# USB.net
KiCad netlist of a schematic drawn in Altium Designer
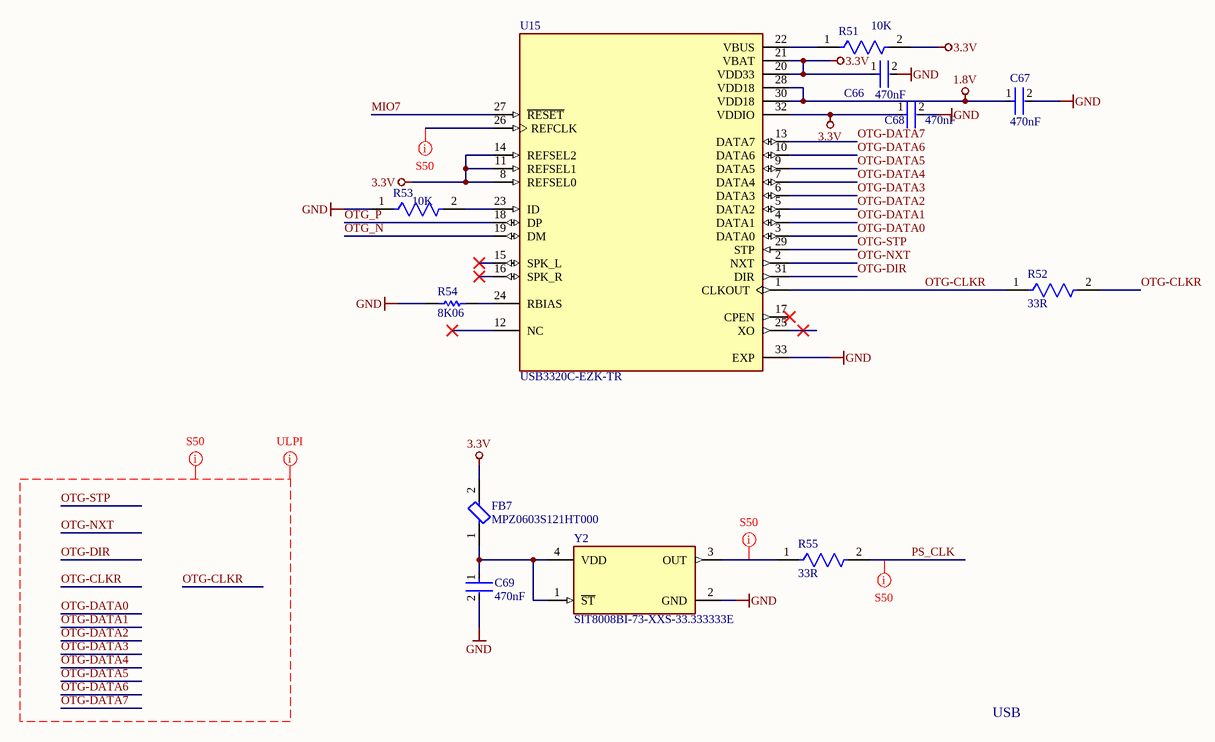
[diagram p0: USB.SchDoc]

(export (version "E")
  (design (tool "Eeschema 10.0.6"))
  (components
    (comp (ref "C66")
      (value "470nF")
      (footprint "FP-GRM15-0_1-MFG")
      (description "CAP CER 0.47UF 10V X5R 0402")
      (fields
        (field (name "MANUFACTURER") "Murata Electronics North America")
        (field (name "MANUFACTURER PART NUMBER") "GRM155R61A474KE15D")
      )
      (libsource (lib "Altium Content Vault") (part "11868f565c42a9108669ba33697ecf6"))
    )
    (comp (ref "C67")
      (value "470nF")
      (footprint "FP-GRM15-0_1-MFG")
      (description "CAP CER 0.47UF 10V X5R 0402")
      (fields
        (field (name "MANUFACTURER") "Murata Electronics North America")
        (field (name "MANUFACTURER PART NUMBER") "GRM155R61A474KE15D")
      )
      (libsource (lib "Altium Content Vault") (part "11868f565c42a9108669ba33697ecf6"))
    )
    (comp (ref "C68")
      (value "470nF")
      (footprint "FP-GRM15-0_1-MFG")
      (description "CAP CER 0.47UF 10V X5R 0402")
      (fields
        (field (name "MANUFACTURER") "Murata Electronics North America")
        (field (name "MANUFACTURER PART NUMBER") "GRM155R61A474KE15D")
      )
      (libsource (lib "Altium Content Vault") (part "11868f565c42a9108669ba33697ecf6"))
    )
    (comp (ref "C69")
      (value "470nF")
      (footprint "FP-GRM15-0_1-MFG")
      (description "CAP CER 0.47UF 10V X5R 0402")
      (fields
        (field (name "MANUFACTURER") "Murata Electronics North America")
        (field (name "MANUFACTURER PART NUMBER") "GRM155R61A474KE15D")
      )
      (libsource (lib "Altium Content Vault") (part "11868f565c42a9108669ba33697ecf6"))
    )
    (comp (ref "FB7")
      (value "MPZ0603S121HT000")
      (footprint "FP-MPZ0603-IPC_C")
      (description "CHIP BEADS FOR GENERAL SIGNAL LI")
      (libsource (lib "Altium Content Vault") (part "5f30dd21d616792df468990f7003faa"))
    )
    (comp (ref "R51")
      (value "10K")
      (footprint "FP-MCT0603-IPC_C")
      (description "RES SMD 100 OHM 1% 1/8W 0603")
      (libsource (lib "Altium Content Vault") (part "1029c3af85768c4190bb7ad29bc67b5"))
    )
    (comp (ref "R52")
      (value "33R")
      (footprint "FP-AC0603-IPC_A")
      (description "RES 33Ω 1.00% 0.1W 0603")
      (fields (field (name "TOLERANCE") "1%"))
      (libsource (lib "Altium Content Vault") (part "1029c3af85768c4190bb7ad29bc67b5"))
    )
    (comp (ref "R53")
      (value "10K")
      (footprint "FP-MCT0603-IPC_C")
      (description "RES SMD 100 OHM 1% 1/8W 0603")
      (libsource (lib "Altium Content Vault") (part "1029c3af85768c4190bb7ad29bc67b5"))
    )
    (comp (ref "R54")
      (value "8K06")
      (footprint "RESC0603(1608)_N")
      (description "8K06 0.1W 1% 0603 (1608 Metric)  SMD")
      (fields (field (name "POWER") "0.1 W") (field (name "TOLERANCE") "1 %"))
      (libsource (lib "Altium Content Vault") (part "RES"))
    )
    (comp (ref "R55")
      (value "33R")
      (footprint "FP-AC0603-IPC_A")
      (description "RES 33Ω 1.00% 0.1W 0603")
      (fields (field (name "TOLERANCE") "1%"))
      (libsource (lib "Altium Content Vault") (part "1029c3af85768c4190bb7ad29bc67b5"))
    )
    (comp (ref "U15")
      (value "USB3320C-EZK-TR")
      (footprint "QFN50P500X500X100-33N")
      (fields (field (name "MF") "Microchip"))
      (libsource (lib "USB3320C-EZK-TR") (part "USB3320C-EZK-TR"))
    )
    (comp (ref "Y2")
      (value "SIT8008BI-73-XXS-33.333333E")
      (footprint "FP-SiT8008-7-MFG")
      (description "MEMS OSC XO 33.333333MHZ H/LV-CM")
      (libsource (lib "Altium Content Vault") (part "608760d4db080d87b5a53965dd36a1f"))
    )
  )
  (nets
    (net (code "1") (name "/MIO7") (class "Default")
      (node (ref "U15") (pin "27") (pinfunction "~{RESET}_27") (pintype "input"))
    )
    (net (code "2") (name "/OTG-CLKR") (class "Default")
      (node (ref "R52") (pin "1") (pinfunction "1_1") (pintype "passive"))
      (node (ref "R52") (pin "2") (pinfunction "2_2") (pintype "passive"))
      (node (ref "U15") (pin "1") (pinfunction "CLKOUT_1") (pintype "output"))
    )
    (net (code "3") (name "/OTG-DATA0") (class "Default")
      (node (ref "U15") (pin "3") (pinfunction "DATA0_3") (pintype "bidirectional"))
    )
    (net (code "4") (name "/OTG-DATA1") (class "Default")
      (node (ref "U15") (pin "4") (pinfunction "DATA1_4") (pintype "bidirectional"))
    )
    (net (code "5") (name "/OTG-DATA2") (class "Default")
      (node (ref "U15") (pin "5") (pinfunction "DATA2_5") (pintype "bidirectional"))
    )
    (net (code "6") (name "/OTG-DATA3") (class "Default")
      (node (ref "U15") (pin "6") (pinfunction "DATA3_6") (pintype "bidirectional"))
    )
    (net (code "7") (name "/OTG-DATA4") (class "Default")
      (node (ref "U15") (pin "7") (pinfunction "DATA4_7") (pintype "bidirectional"))
    )
    (net (code "8") (name "/OTG-DATA5") (class "Default")
      (node (ref "U15") (pin "9") (pinfunction "DATA5_9") (pintype "bidirectional"))
    )
    (net (code "9") (name "/OTG-DATA6") (class "Default")
      (node (ref "U15") (pin "10") (pinfunction "DATA6_10") (pintype "bidirectional"))
    )
    (net (code "10") (name "/OTG-DATA7") (class "Default")
      (node (ref "U15") (pin "13") (pinfunction "DATA7_13") (pintype "bidirectional"))
    )
    (net (code "11") (name "/OTG-DIR") (class "Default")
      (node (ref "U15") (pin "31") (pinfunction "DIR_31") (pintype "output"))
    )
    (net (code "12") (name "/OTG-NXT") (class "Default")
      (node (ref "U15") (pin "2") (pinfunction "NXT_2") (pintype "output"))
    )
    (net (code "13") (name "/OTG-STP") (class "Default")
      (node (ref "U15") (pin "29") (pinfunction "STP_29") (pintype "input"))
    )
    (net (code "14") (name "/OTG_N") (class "Default")
      (node (ref "U15") (pin "19") (pinfunction "DM_19") (pintype "bidirectional"))
    )
    (net (code "15") (name "/OTG_P") (class "Default")
      (node (ref "U15") (pin "18") (pinfunction "DP_18") (pintype "bidirectional"))
    )
    (net (code "16") (name "/PS_CLK") (class "Default")
      (node (ref "R55") (pin "2") (pinfunction "2_2") (pintype "passive"))
    )
    (net (code "17") (name "1.8V") (class "Default")
      (node (ref "C67") (pin "1") (pinfunction "1_1") (pintype "passive"))
      (node (ref "U15") (pin "28") (pinfunction "VDD18_28") (pintype "power_in"))
      (node (ref "U15") (pin "30") (pinfunction "VDD18_30") (pintype "power_in"))
    )
    (net (code "18") (name "3.3V") (class "Default")
      (node (ref "C66") (pin "1") (pinfunction "1_1") (pintype "passive"))
      (node (ref "C68") (pin "1") (pinfunction "1_1") (pintype "passive"))
      (node (ref "FB7") (pin "2") (pinfunction "2_2") (pintype "passive"))
      (node (ref "R51") (pin "2") (pinfunction "2_2") (pintype "passive"))
      (node (ref "U15") (pin "11") (pinfunction "REFSEL1_11") (pintype "input"))
      (node (ref "U15") (pin "14") (pinfunction "REFSEL2_14") (pintype "input"))
      (node (ref "U15") (pin "20") (pinfunction "VDD33_20") (pintype "power_in"))
      (node (ref "U15") (pin "21") (pinfunction "VBAT_21") (pintype "power_in"))
      (node (ref "U15") (pin "32") (pinfunction "VDDIO_32") (pintype "power_in"))
      (node (ref "U15") (pin "8") (pinfunction "REFSEL0_8") (pintype "input"))
    )
    (net (code "19") (name "GND") (class "Default")
      (node (ref "C66") (pin "2") (pinfunction "2_2") (pintype "passive"))
      (node (ref "C67") (pin "2") (pinfunction "2_2") (pintype "passive"))
      (node (ref "C68") (pin "2") (pinfunction "2_2") (pintype "passive"))
      (node (ref "C69") (pin "2") (pinfunction "2_2") (pintype "passive"))
      (node (ref "R53") (pin "1") (pinfunction "1_1") (pintype "passive"))
      (node (ref "R54") (pin "1") (pinfunction "1_1") (pintype "passive"))
      (node (ref "U15") (pin "33") (pinfunction "EXP_33") (pintype "power_in"))
      (node (ref "Y2") (pin "2") (pinfunction "GND_2") (pintype "power_in"))
    )
    (net (code "20") (name "Net-(U15-ID)") (class "Default")
      (node (ref "R53") (pin "2") (pinfunction "2_2") (pintype "passive"))
      (node (ref "U15") (pin "23") (pinfunction "ID_23") (pintype "input"))
    )
    (net (code "21") (name "Net-(U15-RBIAS)") (class "Default")
      (node (ref "R54") (pin "2") (pinfunction "2_2") (pintype "passive"))
      (node (ref "U15") (pin "24") (pinfunction "RBIAS_24") (pintype "passive"))
    )
    (net (code "22") (name "Net-(U15-VBUS)") (class "Default")
      (node (ref "R51") (pin "1") (pinfunction "1_1") (pintype "passive"))
      (node (ref "U15") (pin "22") (pinfunction "VBUS_22") (pintype "power_in"))
    )
    (net (code "23") (name "Net-(Y2-OUT)") (class "Default")
      (node (ref "R55") (pin "1") (pinfunction "1_1") (pintype "passive"))
      (node (ref "Y2") (pin "3") (pinfunction "OUT_3") (pintype "output"))
    )
    (net (code "24") (name "Net-(Y2-VDD)") (class "Default")
      (node (ref "C69") (pin "1") (pinfunction "1_1") (pintype "passive"))
      (node (ref "FB7") (pin "1") (pinfunction "1_1") (pintype "passive"))
      (node (ref "Y2") (pin "1") (pinfunction "~{ST}_1") (pintype "input"))
      (node (ref "Y2") (pin "4") (pinfunction "VDD_4") (pintype "power_in"))
    )
    (net (code "25") (name "unconnected-(U15-CPEN-Pad17)") (class "Default")
      (node (ref "U15") (pin "17") (pinfunction "CPEN_17") (pintype "output+no_connect"))
    )
    (net (code "26") (name "unconnected-(U15-NC-Pad12)") (class "Default")
      (node (ref "U15") (pin "12") (pinfunction "NC_12") (pintype "passive+no_connect"))
    )
    (net (code "27") (name "unconnected-(U15-REFCLK-Pad26)") (class "Default")
      (node (ref "U15") (pin "26") (pinfunction "REFCLK_26") (pintype "input"))
    )
    (net (code "28") (name "unconnected-(U15-SPK_L-Pad15)") (class "Default")
      (node (ref "U15") (pin "15") (pinfunction "SPK_L_15") (pintype "bidirectional+no_connect"))
    )
    (net (code "29") (name "unconnected-(U15-SPK_R-Pad16)") (class "Default")
      (node (ref "U15") (pin "16") (pinfunction "SPK_R_16") (pintype "bidirectional+no_connect"))
    )
    (net (code "30") (name "unconnected-(U15-XO-Pad25)") (class "Default")
      (node (ref "U15") (pin "25") (pinfunction "XO_25") (pintype "output"))
    )
  )
)
